# SCH_reciver.net
KiCad netlist of a schematic drawn in EasyEDA
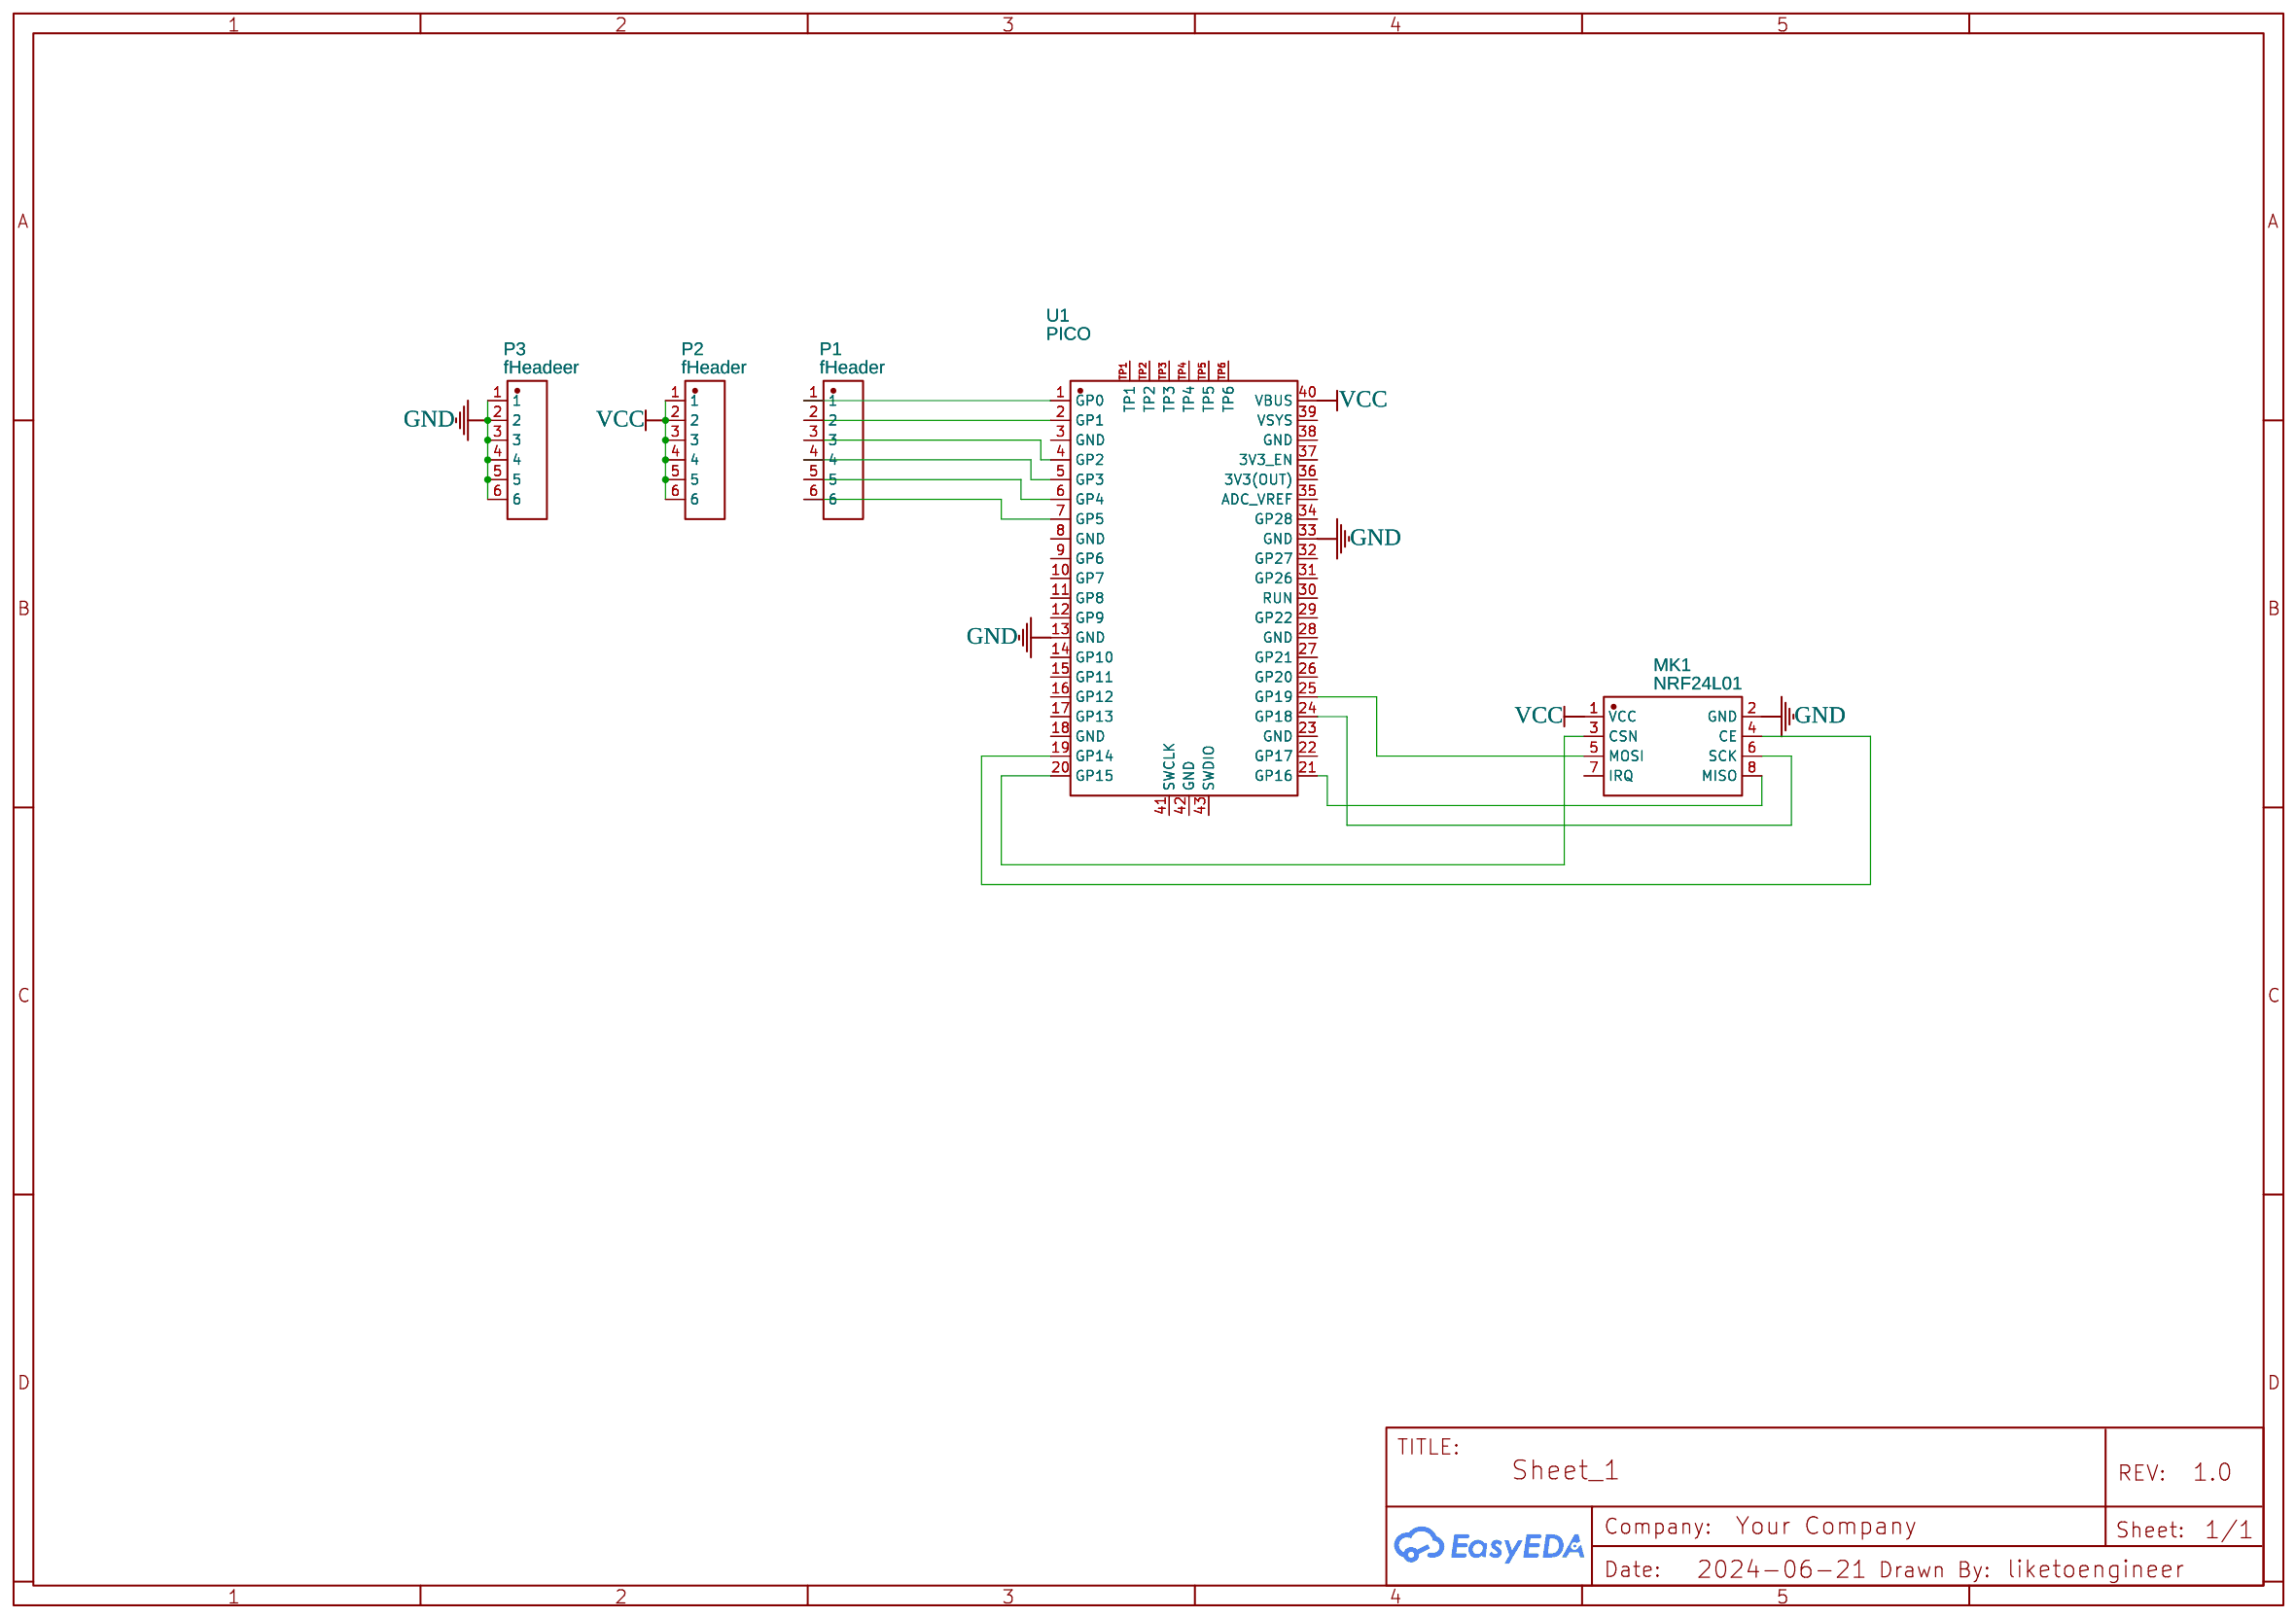
[diagram p0: schematic sheet]

(export (version "E")
  (design (tool "Eeschema 10.0.6"))
  (components
    (comp (ref "MK1")
      (value "NRF24L01")
      (fields (field (name "Manufacturer Part") "NF-04") (field (name "Manufacturer") "Ai-Thinker(安信可)"))
      (libsource (lib "") (part "NRF24L01"))
    )
    (comp (ref "P1")
      (value "fHeader")
      (fields (field (name "Manufacturer Part") "2.54-1*6P母") (field (name "Manufacturer") "BOOMELE(博穆精密)"))
      (libsource (lib "") (part "Header-Female-2.54_1x6"))
    )
    (comp (ref "P2")
      (value "fHeader")
      (fields (field (name "Manufacturer Part") "2.54-1*6P母") (field (name "Manufacturer") "BOOMELE(博穆精密)"))
      (libsource (lib "") (part "Header-Female-2.54_1x6"))
    )
    (comp (ref "P3")
      (value "fHeadeer")
      (fields (field (name "Manufacturer Part") "2.54-1*6P母") (field (name "Manufacturer") "BOOMELE(博穆精密)"))
      (libsource (lib "") (part "Header-Female-2.54_1x6"))
    )
    (comp (ref "U1")
      (value "PICO")
      (fields (field (name "Manufacturer") "Raspberry Pi(树莓派)"))
      (libsource (lib "") (part "PICO"))
    )
  )
  (nets
    (net (code "1") (name "GND") (class "Default")
      (node (ref "MK1") (pin "2") (pinfunction "GND_2") (pintype "unspecified"))
      (node (ref "P3") (pin "1") (pinfunction "1_1") (pintype "unspecified"))
      (node (ref "P3") (pin "2") (pinfunction "2_2") (pintype "unspecified"))
      (node (ref "P3") (pin "3") (pinfunction "3_3") (pintype "unspecified"))
      (node (ref "P3") (pin "4") (pinfunction "4_4") (pintype "unspecified"))
      (node (ref "P3") (pin "5") (pinfunction "5_5") (pintype "unspecified"))
      (node (ref "P3") (pin "6") (pinfunction "6_6") (pintype "unspecified"))
      (node (ref "U1") (pin "13") (pinfunction "GND_13") (pintype "unspecified"))
      (node (ref "U1") (pin "33") (pinfunction "GND_33") (pintype "unspecified"))
    )
    (net (code "2") (name "Net-(MK1-CE)") (class "Default")
      (node (ref "MK1") (pin "4") (pinfunction "CE_4") (pintype "unspecified"))
      (node (ref "U1") (pin "19") (pinfunction "GP14_19") (pintype "unspecified"))
    )
    (net (code "3") (name "Net-(MK1-CSN)") (class "Default")
      (node (ref "MK1") (pin "3") (pinfunction "CSN_3") (pintype "unspecified"))
      (node (ref "U1") (pin "20") (pinfunction "GP15_20") (pintype "unspecified"))
    )
    (net (code "4") (name "Net-(MK1-MISO)") (class "Default")
      (node (ref "MK1") (pin "8") (pinfunction "MISO_8") (pintype "unspecified"))
      (node (ref "U1") (pin "21") (pinfunction "GP16_21") (pintype "unspecified"))
    )
    (net (code "5") (name "Net-(MK1-MOSI)") (class "Default")
      (node (ref "MK1") (pin "5") (pinfunction "MOSI_5") (pintype "unspecified"))
      (node (ref "U1") (pin "25") (pinfunction "GP19_25") (pintype "unspecified"))
    )
    (net (code "6") (name "Net-(MK1-SCK)") (class "Default")
      (node (ref "MK1") (pin "6") (pinfunction "SCK_6") (pintype "unspecified"))
      (node (ref "U1") (pin "24") (pinfunction "GP18_24") (pintype "unspecified"))
    )
    (net (code "7") (name "Net-(U1-GP0)") (class "Default")
      (node (ref "P1") (pin "1") (pinfunction "1_1") (pintype "unspecified"))
      (node (ref "U1") (pin "1") (pinfunction "GP0_1") (pintype "unspecified"))
    )
    (net (code "8") (name "Net-(U1-GP1)") (class "Default")
      (node (ref "P1") (pin "2") (pinfunction "2_2") (pintype "unspecified"))
      (node (ref "U1") (pin "2") (pinfunction "GP1_2") (pintype "unspecified"))
    )
    (net (code "9") (name "Net-(U1-GP2)") (class "Default")
      (node (ref "P1") (pin "3") (pinfunction "3_3") (pintype "unspecified"))
      (node (ref "U1") (pin "4") (pinfunction "GP2_4") (pintype "unspecified"))
    )
    (net (code "10") (name "Net-(U1-GP3)") (class "Default")
      (node (ref "P1") (pin "4") (pinfunction "4_4") (pintype "unspecified"))
      (node (ref "U1") (pin "5") (pinfunction "GP3_5") (pintype "unspecified"))
    )
    (net (code "11") (name "Net-(U1-GP4)") (class "Default")
      (node (ref "P1") (pin "5") (pinfunction "5_5") (pintype "unspecified"))
      (node (ref "U1") (pin "6") (pinfunction "GP4_6") (pintype "unspecified"))
    )
    (net (code "12") (name "Net-(U1-GP5)") (class "Default")
      (node (ref "P1") (pin "6") (pinfunction "6_6") (pintype "unspecified"))
      (node (ref "U1") (pin "7") (pinfunction "GP5_7") (pintype "unspecified"))
    )
    (net (code "13") (name "VCC") (class "Default")
      (node (ref "MK1") (pin "1") (pinfunction "VCC_1") (pintype "unspecified"))
      (node (ref "P2") (pin "1") (pinfunction "1_1") (pintype "unspecified"))
      (node (ref "P2") (pin "2") (pinfunction "2_2") (pintype "unspecified"))
      (node (ref "P2") (pin "3") (pinfunction "3_3") (pintype "unspecified"))
      (node (ref "P2") (pin "4") (pinfunction "4_4") (pintype "unspecified"))
      (node (ref "P2") (pin "5") (pinfunction "5_5") (pintype "unspecified"))
      (node (ref "P2") (pin "6") (pinfunction "6_6") (pintype "unspecified"))
      (node (ref "U1") (pin "40") (pinfunction "VBUS_40") (pintype "unspecified"))
    )
    (net (code "14") (name "unconnected-(MK1-IRQ-Pad7)") (class "Default")
      (node (ref "MK1") (pin "7") (pinfunction "IRQ_7") (pintype "unspecified"))
    )
    (net (code "15") (name "unconnected-(U1-3V3(OUT)-Pad36)") (class "Default")
      (node (ref "U1") (pin "36") (pinfunction "3V3(OUT)_36") (pintype "unspecified"))
    )
    (net (code "16") (name "unconnected-(U1-3V3_EN-Pad37)") (class "Default")
      (node (ref "U1") (pin "37") (pinfunction "3V3_EN_37") (pintype "unspecified"))
    )
    (net (code "17") (name "unconnected-(U1-ADC_VREF-Pad35)") (class "Default")
      (node (ref "U1") (pin "35") (pinfunction "ADC_VREF_35") (pintype "unspecified"))
    )
    (net (code "18") (name "unconnected-(U1-GND-Pad3)") (class "Default")
      (node (ref "U1") (pin "3") (pinfunction "GND_3") (pintype "unspecified"))
    )
    (net (code "19") (name "unconnected-(U1-GND-Pad8)") (class "Default")
      (node (ref "U1") (pin "8") (pinfunction "GND_8") (pintype "unspecified"))
    )
    (net (code "20") (name "unconnected-(U1-GND-Pad18)") (class "Default")
      (node (ref "U1") (pin "18") (pinfunction "GND_18") (pintype "unspecified"))
    )
    (net (code "21") (name "unconnected-(U1-GND-Pad23)") (class "Default")
      (node (ref "U1") (pin "23") (pinfunction "GND_23") (pintype "unspecified"))
    )
    (net (code "22") (name "unconnected-(U1-GND-Pad28)") (class "Default")
      (node (ref "U1") (pin "28") (pinfunction "GND_28") (pintype "unspecified"))
    )
    (net (code "23") (name "unconnected-(U1-GND-Pad38)") (class "Default")
      (node (ref "U1") (pin "38") (pinfunction "GND_38") (pintype "unspecified"))
    )
    (net (code "24") (name "unconnected-(U1-GND-Pad42)") (class "Default")
      (node (ref "U1") (pin "42") (pinfunction "GND_42") (pintype "unspecified"))
    )
    (net (code "25") (name "unconnected-(U1-GP6-Pad9)") (class "Default")
      (node (ref "U1") (pin "9") (pinfunction "GP6_9") (pintype "unspecified"))
    )
    (net (code "26") (name "unconnected-(U1-GP7-Pad10)") (class "Default")
      (node (ref "U1") (pin "10") (pinfunction "GP7_10") (pintype "unspecified"))
    )
    (net (code "27") (name "unconnected-(U1-GP8-Pad11)") (class "Default")
      (node (ref "U1") (pin "11") (pinfunction "GP8_11") (pintype "unspecified"))
    )
    (net (code "28") (name "unconnected-(U1-GP9-Pad12)") (class "Default")
      (node (ref "U1") (pin "12") (pinfunction "GP9_12") (pintype "unspecified"))
    )
    (net (code "29") (name "unconnected-(U1-GP10-Pad14)") (class "Default")
      (node (ref "U1") (pin "14") (pinfunction "GP10_14") (pintype "unspecified"))
    )
    (net (code "30") (name "unconnected-(U1-GP11-Pad15)") (class "Default")
      (node (ref "U1") (pin "15") (pinfunction "GP11_15") (pintype "unspecified"))
    )
    (net (code "31") (name "unconnected-(U1-GP12-Pad16)") (class "Default")
      (node (ref "U1") (pin "16") (pinfunction "GP12_16") (pintype "unspecified"))
    )
    (net (code "32") (name "unconnected-(U1-GP13-Pad17)") (class "Default")
      (node (ref "U1") (pin "17") (pinfunction "GP13_17") (pintype "unspecified"))
    )
    (net (code "33") (name "unconnected-(U1-GP17-Pad22)") (class "Default")
      (node (ref "U1") (pin "22") (pinfunction "GP17_22") (pintype "unspecified"))
    )
    (net (code "34") (name "unconnected-(U1-GP20-Pad26)") (class "Default")
      (node (ref "U1") (pin "26") (pinfunction "GP20_26") (pintype "unspecified"))
    )
    (net (code "35") (name "unconnected-(U1-GP21-Pad27)") (class "Default")
      (node (ref "U1") (pin "27") (pinfunction "GP21_27") (pintype "unspecified"))
    )
    (net (code "36") (name "unconnected-(U1-GP22-Pad29)") (class "Default")
      (node (ref "U1") (pin "29") (pinfunction "GP22_29") (pintype "unspecified"))
    )
    (net (code "37") (name "unconnected-(U1-GP26-Pad31)") (class "Default")
      (node (ref "U1") (pin "31") (pinfunction "GP26_31") (pintype "unspecified"))
    )
    (net (code "38") (name "unconnected-(U1-GP27-Pad32)") (class "Default")
      (node (ref "U1") (pin "32") (pinfunction "GP27_32") (pintype "unspecified"))
    )
    (net (code "39") (name "unconnected-(U1-GP28-Pad34)") (class "Default")
      (node (ref "U1") (pin "34") (pinfunction "GP28_34") (pintype "unspecified"))
    )
    (net (code "40") (name "unconnected-(U1-PadTP1)") (class "Default")
      (node (ref "U1") (pin "TP1") (pinfunction "TP1_TP1") (pintype "unspecified"))
    )
    (net (code "41") (name "unconnected-(U1-PadTP2)") (class "Default")
      (node (ref "U1") (pin "TP2") (pinfunction "TP2_TP2") (pintype "unspecified"))
    )
    (net (code "42") (name "unconnected-(U1-PadTP3)") (class "Default")
      (node (ref "U1") (pin "TP3") (pinfunction "TP3_TP3") (pintype "unspecified"))
    )
    (net (code "43") (name "unconnected-(U1-PadTP4)") (class "Default")
      (node (ref "U1") (pin "TP4") (pinfunction "TP4_TP4") (pintype "unspecified"))
    )
    (net (code "44") (name "unconnected-(U1-PadTP5)") (class "Default")
      (node (ref "U1") (pin "TP5") (pinfunction "TP5_TP5") (pintype "unspecified"))
    )
    (net (code "45") (name "unconnected-(U1-PadTP6)") (class "Default")
      (node (ref "U1") (pin "TP6") (pinfunction "TP6_TP6") (pintype "unspecified"))
    )
    (net (code "46") (name "unconnected-(U1-RUN-Pad30)") (class "Default")
      (node (ref "U1") (pin "30") (pinfunction "RUN_30") (pintype "unspecified"))
    )
    (net (code "47") (name "unconnected-(U1-SWCLK-Pad41)") (class "Default")
      (node (ref "U1") (pin "41") (pinfunction "SWCLK_41") (pintype "unspecified"))
    )
    (net (code "48") (name "unconnected-(U1-SWDIO-Pad43)") (class "Default")
      (node (ref "U1") (pin "43") (pinfunction "SWDIO_43") (pintype "unspecified"))
    )
    (net (code "49") (name "unconnected-(U1-VSYS-Pad39)") (class "Default")
      (node (ref "U1") (pin "39") (pinfunction "VSYS_39") (pintype "unspecified"))
    )
  )
)
